# bob.net
KiCad netlist of a schematic drawn in Altium Designer
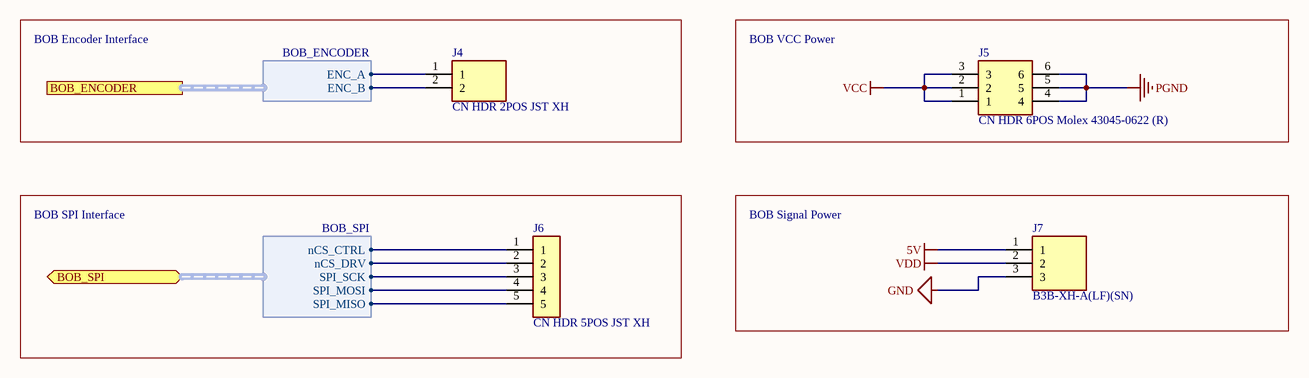
[diagram p0: bob.SchDoc]

(export (version "E")
  (design (tool "Eeschema 10.0.6"))
  (components
    (comp (ref "J4")
      (value "CN HDR 2POS JST XH")
      (footprint "JST_B2B-XH-A(LF)(SN)")
      (description "Connector Header Through Hole 2 position 0.098 _2.50mm_\r\nJST XH")
      (fields (field (name "MP") "B2B-XH-A_LF__SN_") (field (name "MF") "JST Sales"))
      (libsource (lib "AltiumLibraries") (part "CN HDR 2POS JST XH"))
    )
    (comp (ref "J5")
      (value "CN HDR 6POS Molex 43045-0622 (R)")
      (footprint "430450622")
      (description "Molex 43045-0622 6POS Microfit\r\ndual row, right angle")
      (libsource (lib "AltiumLibraries") (part "CN HDR 6POS Molex 43045-0622 (R)"))
    )
    (comp (ref "J6")
      (value "CN HDR 5POS JST XH")
      (footprint "JST_B5B-XH-A(LF)(SN)")
      (description "Connector Header Through Hole 5 position 0.098\" (2.50mm)")
      (fields (field (name "MP") "B5B-XH-A(LF)(SN)") (field (name "MF") "JST Sales"))
      (libsource (lib "AltiumLibraries") (part "CN HDR 5POS JST XH"))
    )
    (comp (ref "J7")
      (value "B3B-XH-A(LF)(SN)")
      (footprint "JST_B3B-XH-A(LF)(SN)")
      (description "CN 3POS TH JST XH")
      (fields (field (name "MF") "JST Sales"))
      (libsource (lib "AltiumLibraries") (part "CN 3POS TH JSTXH"))
    )
  )
  (nets
    (net (code "3") (name "/ENC_A") (class "Default")
      (node (ref "J4") (pin "1") (pinfunction "1_1") (pintype "passive"))
    )
    (net (code "4") (name "/ENC_B") (class "Default")
      (node (ref "J4") (pin "2") (pinfunction "2_2") (pintype "passive"))
    )
    (net (code "5") (name "/SPI_MISO") (class "Default")
      (node (ref "J6") (pin "5") (pinfunction "5_5") (pintype "passive"))
    )
    (net (code "6") (name "/SPI_MOSI") (class "Default")
      (node (ref "J6") (pin "4") (pinfunction "4_4") (pintype "passive"))
    )
    (net (code "7") (name "/SPI_SCK") (class "Default")
      (node (ref "J6") (pin "3") (pinfunction "3_3") (pintype "passive"))
    )
    (net (code "8") (name "/nCS_CTRL") (class "Default")
      (node (ref "J6") (pin "1") (pinfunction "1_1") (pintype "passive"))
    )
    (net (code "9") (name "/nCS_DRV") (class "Default")
      (node (ref "J6") (pin "2") (pinfunction "2_2") (pintype "passive"))
    )
    (net (code "12") (name "5V") (class "Default")
      (node (ref "J7") (pin "1") (pinfunction "1_1") (pintype "passive"))
    )
    (net (code "13") (name "GND") (class "Default")
      (node (ref "J7") (pin "3") (pinfunction "3_3") (pintype "passive"))
    )
    (net (code "14") (name "PGND") (class "Default")
      (node (ref "J5") (pin "4") (pinfunction "4_4") (pintype "passive"))
      (node (ref "J5") (pin "5") (pinfunction "5_5") (pintype "passive"))
      (node (ref "J5") (pin "6") (pinfunction "6_6") (pintype "passive"))
    )
    (net (code "15") (name "VCC") (class "Default")
      (node (ref "J5") (pin "1") (pinfunction "1_1") (pintype "passive"))
      (node (ref "J5") (pin "2") (pinfunction "2_2") (pintype "passive"))
      (node (ref "J5") (pin "3") (pinfunction "3_3") (pintype "passive"))
    )
    (net (code "16") (name "VDD") (class "Default")
      (node (ref "J7") (pin "2") (pinfunction "2_2") (pintype "passive"))
    )
  )
)
